# NB-Blue.net
KiCad netlist of a schematic drawn in Altium Designer
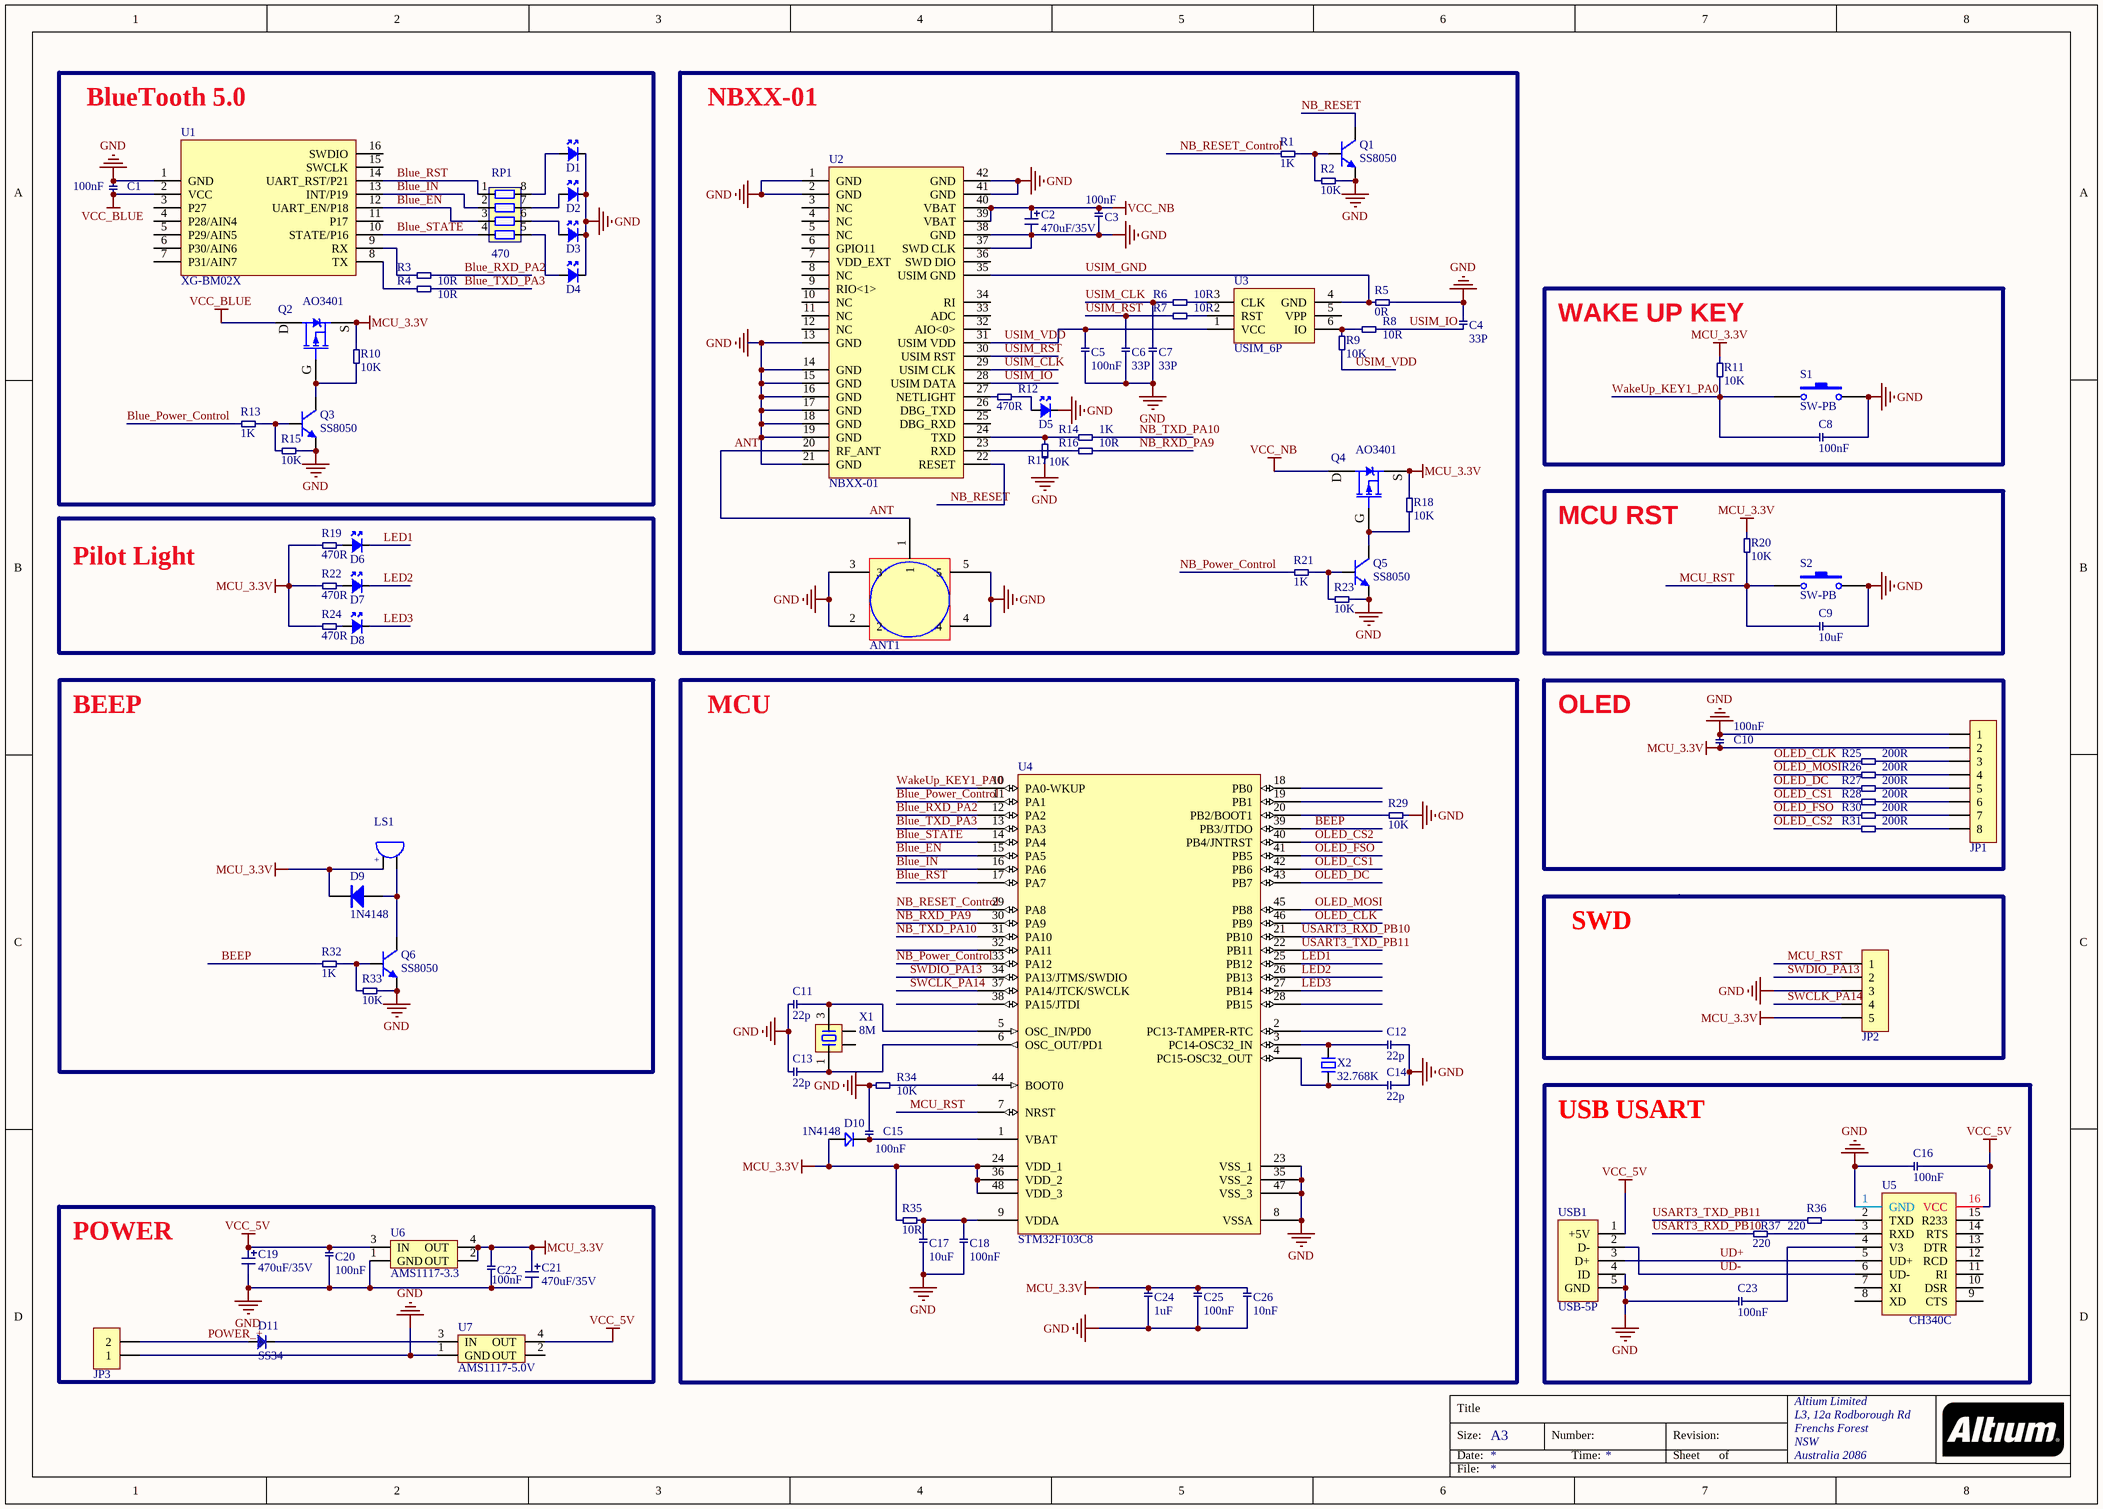
[diagram p0: NB-Blue.SchDoc]

(export (version "E")
  (design (tool "Eeschema 10.0.6"))
  (components
    (comp (ref "ANT1")
      (value "ANT")
      (footprint "SMA_FR")
      (description "SMA天线座")
      (libsource (lib "转接板顶板") (part "ANT"))
    )
    (comp (ref "C1") (value "100nF") (footprint "0603CC") (libsource (lib "LFZ@WLP") (part "cap")))
    (comp (ref "C2") (value "470uF/35V") (footprint "C3216") (libsource (lib "LFZ@WLP") (part "Ecap")))
    (comp (ref "C3") (value "100nF") (footprint "0603CC") (libsource (lib "LFZ@WLP") (part "cap")))
    (comp (ref "C4") (value "33P") (footprint "0603CC") (libsource (lib "LFZ@WLP") (part "cap")))
    (comp (ref "C5") (value "100nF") (footprint "0603CC") (libsource (lib "LFZ@WLP") (part "cap")))
    (comp (ref "C6") (value "33P") (footprint "0603CC") (libsource (lib "LFZ@WLP") (part "cap")))
    (comp (ref "C7") (value "33P") (footprint "0603CC") (libsource (lib "LFZ@WLP") (part "cap")))
    (comp (ref "C8") (value "100nF") (footprint "0603CC") (libsource (lib "LFZ@WLP") (part "cap")))
    (comp (ref "C9") (value "10uF") (footprint "0603CC") (libsource (lib "LFZ@WLP") (part "cap")))
    (comp (ref "C10") (value "100nF") (footprint "0603CC") (libsource (lib "LFZ@WLP") (part "cap")))
    (comp (ref "C11") (value "22p") (footprint "0603CC") (libsource (lib "LFZ@WLP") (part "cap")))
    (comp (ref "C12") (value "22p") (footprint "0603CC") (libsource (lib "LFZ@WLP") (part "cap")))
    (comp (ref "C13") (value "22p") (footprint "0603CC") (libsource (lib "LFZ@WLP") (part "cap")))
    (comp (ref "C14") (value "22p") (footprint "0603CC") (libsource (lib "LFZ@WLP") (part "cap")))
    (comp (ref "C15") (value "100nF") (footprint "0603CC") (libsource (lib "LFZ@WLP") (part "cap")))
    (comp (ref "C16") (value "100nF") (footprint "0603CC") (libsource (lib "LFZ@WLP") (part "cap")))
    (comp (ref "C17") (value "10uF") (footprint "0603CC") (libsource (lib "LFZ@WLP") (part "cap")))
    (comp (ref "C18") (value "100nF") (footprint "0603CC") (libsource (lib "LFZ@WLP") (part "cap")))
    (comp (ref "C19") (value "470uF/35V") (footprint "CD A(3216)") (libsource (lib "LFZ@WLP") (part "Ecap")))
    (comp (ref "C20") (value "100nF") (footprint "0603CC") (libsource (lib "LFZ@WLP") (part "cap")))
    (comp (ref "C21") (value "470uF/35V") (footprint "C3216") (libsource (lib "LFZ@WLP") (part "Ecap")))
    (comp (ref "C22") (value "100nF") (footprint "0603CC") (libsource (lib "LFZ@WLP") (part "cap")))
    (comp (ref "C23") (value "100nF") (footprint "0603CC") (libsource (lib "LFZ@WLP") (part "cap")))
    (comp (ref "C24") (value "1uF") (footprint "0603CC") (libsource (lib "LFZ@WLP") (part "cap")))
    (comp (ref "C25") (value "100nF") (footprint "0603CC") (libsource (lib "LFZ@WLP") (part "cap")))
    (comp (ref "C26") (value "10nF") (footprint "0603CC") (libsource (lib "LFZ@WLP") (part "cap")))
    (comp (ref "D1") (value "LED") (footprint "LED 0603G") (libsource (lib "LFZ@WLP") (part "LED")))
    (comp (ref "D2") (value "LED") (footprint "LED 0603G") (libsource (lib "LFZ@WLP") (part "LED")))
    (comp (ref "D3") (value "LED") (footprint "LED 0603G") (libsource (lib "LFZ@WLP") (part "LED")))
    (comp (ref "D4") (value "LED") (footprint "LED 0603G") (libsource (lib "LFZ@WLP") (part "LED")))
    (comp (ref "D5") (value "LED") (footprint "LED 0603G") (libsource (lib "LFZ@WLP") (part "LED")))
    (comp (ref "D6") (value "LED") (footprint "LED 3MM-G") (libsource (lib "LFZ@WLP") (part "LED")))
    (comp (ref "D7") (value "LED") (footprint "LED 3MM-G") (libsource (lib "LFZ@WLP") (part "LED")))
    (comp (ref "D8") (value "LED") (footprint "LED 3MM-G") (libsource (lib "LFZ@WLP") (part "LED")))
    (comp (ref "D9")
      (value "1N4148")
      (footprint "SOD-323")
      (description "高速开关二极管")
      (fields (field (name "版权归属") "源创客"))
      (libsource (lib "8.1   - 二极管-整流桥") (part "1N4148"))
    )
    (comp (ref "D10")
      (value "1N4148")
      (footprint "SOD-323")
      (libsource (lib "WarShip V3 STM32103封装库") (part "D"))
    )
    (comp (ref "D11") (value "SS34") (footprint "SMA") (libsource (lib "Diod") (part "Diod")))
    (comp (ref "JP1")
      (value "HDR-1X8")
      (footprint "HDR2.54-M-LI-8P")
      (description "8P接插件")
      (fields (field (name "版权归属") "源创客"))
      (libsource (lib "4.5   - 接插件-脚距2.54") (part "Header 8"))
    )
    (comp (ref "JP2")
      (value "HDR-1X5")
      (footprint "HDR2.54-LI-5P")
      (description "5P接插件")
      (fields (field (name "版权归属") "源创客"))
      (libsource (lib "4.5   - 接插件-脚距2.54") (part "Header 5"))
    )
    (comp (ref "JP3")
      (value "HDR-1X2")
      (footprint "XH2.54-WI-2P")
      (description "2P接插件")
      (fields (field (name "版权归属") "源创客"))
      (libsource (lib "4.5   - 接插件-脚距2.54") (part "Header 2"))
    )
    (comp (ref "LS1")
      (value "DC5V")
      (footprint "BEEP 5x9x5.5")
      (description "蜂鸣器")
      (fields (field (name "版权归属") "源创客"))
      (libsource (lib "15.1 - 未分类器件") (part "BEEP"))
    )
    (comp (ref "Q1")
      (value "SS8050")
      (footprint "SOT23-3N")
      (description "高频放大-NPN型")
      (fields (field (name "版权归属") "源创客"))
      (libsource (lib "6.2   - 三极管") (part "8050-SMD"))
    )
    (comp (ref "Q2")
      (value "AO3401")
      (footprint "SOT23-3N")
      (description "P沟道场效应管")
      (fields (field (name "版权归属") "源创客"))
      (libsource (lib "6.1   - 场效应管-可控硅") (part "SI2301"))
    )
    (comp (ref "Q3")
      (value "SS8050")
      (footprint "SOT23-3N")
      (description "高频放大-NPN型")
      (fields (field (name "版权归属") "源创客"))
      (libsource (lib "6.2   - 三极管") (part "8050-SMD"))
    )
    (comp (ref "Q4")
      (value "AO3401")
      (footprint "SOT23-3N")
      (description "P沟道场效应管")
      (fields (field (name "版权归属") "源创客"))
      (libsource (lib "6.1   - 场效应管-可控硅") (part "SI2301"))
    )
    (comp (ref "Q5")
      (value "SS8050")
      (footprint "SOT23-3N")
      (description "高频放大-NPN型")
      (fields (field (name "版权归属") "源创客"))
      (libsource (lib "6.2   - 三极管") (part "8050-SMD"))
    )
    (comp (ref "Q6")
      (value "SS8050")
      (footprint "SOT23-3N")
      (description "高频放大-NPN型")
      (fields (field (name "版权归属") "源创客"))
      (libsource (lib "6.2   - 三极管") (part "8050-SMD"))
    )
    (comp (ref "R1") (value "1K") (footprint "0603RR") (libsource (lib "LFZ@WLP") (part "res")))
    (comp (ref "R2") (value "10K") (footprint "0603RR") (libsource (lib "LFZ@WLP") (part "res")))
    (comp (ref "R3") (value "10R") (footprint "0603RR") (libsource (lib "LFZ@WLP") (part "res")))
    (comp (ref "R4") (value "10R") (footprint "0603RR") (libsource (lib "LFZ@WLP") (part "res")))
    (comp (ref "R5") (value "0R") (footprint "0603RR") (libsource (lib "LFZ@WLP") (part "res")))
    (comp (ref "R6") (value "10R") (footprint "0603RR") (libsource (lib "LFZ@WLP") (part "res")))
    (comp (ref "R7") (value "10R") (footprint "0603RR") (libsource (lib "LFZ@WLP") (part "res")))
    (comp (ref "R8") (value "10R") (footprint "0603RR") (libsource (lib "LFZ@WLP") (part "res")))
    (comp (ref "R9") (value "10K") (footprint "0603RR") (libsource (lib "LFZ@WLP") (part "res")))
    (comp (ref "R10") (value "10K") (footprint "0603RR") (libsource (lib "LFZ@WLP") (part "res")))
    (comp (ref "R11") (value "10K") (footprint "0603RR") (libsource (lib "LFZ@WLP") (part "res")))
    (comp (ref "R12") (value "470R") (footprint "0603RR") (libsource (lib "LFZ@WLP") (part "res")))
    (comp (ref "R13") (value "1K") (footprint "0603RR") (libsource (lib "LFZ@WLP") (part "res")))
    (comp (ref "R14") (value "1K") (footprint "0603RR") (libsource (lib "LFZ@WLP") (part "res")))
    (comp (ref "R15") (value "10K") (footprint "0603RR") (libsource (lib "LFZ@WLP") (part "res")))
    (comp (ref "R16") (value "10R") (footprint "0603RR") (libsource (lib "LFZ@WLP") (part "res")))
    (comp (ref "R17") (value "10K") (footprint "0603RR") (libsource (lib "LFZ@WLP") (part "res")))
    (comp (ref "R18") (value "10K") (footprint "0603RR") (libsource (lib "LFZ@WLP") (part "res")))
    (comp (ref "R19") (value "470R") (footprint "0603RR") (libsource (lib "LFZ@WLP") (part "res")))
    (comp (ref "R20") (value "10K") (footprint "0603RR") (libsource (lib "LFZ@WLP") (part "res")))
    (comp (ref "R21") (value "1K") (footprint "0603RR") (libsource (lib "LFZ@WLP") (part "res")))
    (comp (ref "R22") (value "470R") (footprint "0603RR") (libsource (lib "LFZ@WLP") (part "res")))
    (comp (ref "R23") (value "10K") (footprint "0603RR") (libsource (lib "LFZ@WLP") (part "res")))
    (comp (ref "R24") (value "470R") (footprint "0603RR") (libsource (lib "LFZ@WLP") (part "res")))
    (comp (ref "R25") (value "200R") (footprint "0603RR") (libsource (lib "LFZ@WLP") (part "res")))
    (comp (ref "R26") (value "200R") (footprint "0603RR") (libsource (lib "LFZ@WLP") (part "res")))
    (comp (ref "R27") (value "200R") (footprint "0603RR") (libsource (lib "LFZ@WLP") (part "res")))
    (comp (ref "R28") (value "200R") (footprint "0603RR") (libsource (lib "LFZ@WLP") (part "res")))
    (comp (ref "R29") (value "10K") (footprint "0603RR") (libsource (lib "LFZ@WLP") (part "res")))
    (comp (ref "R30") (value "200R") (footprint "0603RR") (libsource (lib "LFZ@WLP") (part "res")))
    (comp (ref "R31") (value "200R") (footprint "0603RR") (libsource (lib "LFZ@WLP") (part "res")))
    (comp (ref "R32") (value "1K") (footprint "0603RR") (libsource (lib "LFZ@WLP") (part "res")))
    (comp (ref "R33") (value "10K") (footprint "0603RR") (libsource (lib "LFZ@WLP") (part "res")))
    (comp (ref "R34") (value "10K") (footprint "0603RR") (libsource (lib "LFZ@WLP") (part "res")))
    (comp (ref "R35") (value "10R") (footprint "0603RR") (libsource (lib "LFZ@WLP") (part "res")))
    (comp (ref "R36") (value "220") (footprint "0603RR") (libsource (lib "LFZ@WLP") (part "res")))
    (comp (ref "R37") (value "220") (footprint "0603RR") (libsource (lib "LFZ@WLP") (part "res")))
    (comp (ref "RP1") (value "470") (footprint "4x0603") (libsource (lib "LFZ@WLP") (part "Resistor_Pack")))
    (comp (ref "S1")
      (value "SW-PB")
      (footprint "TSW SMD-6*6*6")
      (description "Switch")
      (fields (field (name "PUBLISHER") "Altium Limited"))
      (libsource (lib "开关及电源") (part "SW-PB"))
    )
    (comp (ref "S2")
      (value "SW-PB")
      (footprint "TSW SMD-4*4*1.5")
      (description "Switch")
      (fields (field (name "PUBLISHER") "Altium Limited"))
      (libsource (lib "开关及电源") (part "SW-PB"))
    )
    (comp (ref "U1") (value "XG-BM02X") (footprint "XG-BM02X") (libsource (lib "XG-BM02") (part "XG-BM02X")))
    (comp (ref "U2")
      (value "NBXX-01")
      (footprint "X_LSD4NBN-LB05000001")
      (libsource (lib "XG-BM02") (part "NB"))
    )
    (comp (ref "U3") (value "USIM_6P") (footprint "SIM 6P 自弹") (libsource (lib "XG-BM02") (part "USIM-6P")))
    (comp (ref "U4")
      (value "STM32F103C8")
      (footprint "LQFP48 7X7_M")
      (description "Flaah:64/RAM:20/IO:36")
      (fields (field (name "版权归属") "源创客"))
      (libsource (lib "2.1   - STM32系列单片机") (part "STM32F103C8"))
    )
    (comp (ref "U5") (value "CH340C") (footprint "SOP16_L") (libsource (lib "LFZ@WLP") (part "CH340C")))
    (comp (ref "U6")
      (value "AMS1117-3.3")
      (footprint "SOT223_N")
      (libsource (lib "WarShip V3 STM32103封装库") (part "AMS1117"))
    )
    (comp (ref "U7")
      (value "AMS1117-5.0V")
      (footprint "SOT223_N")
      (libsource (lib "WarShip V3 STM32103封装库") (part "AMS1117"))
    )
    (comp (ref "USB1")
      (value "USB-5P")
      (footprint "USB-MICRO_A")
      (description "微型USB母座")
      (fields (field (name "版权归属") "源创客"))
      (libsource (lib "4.1   - 接口类") (part "USB-5P"))
    )
    (comp (ref "X1")
      (value "8M")
      (footprint "OSC 3225-4P")
      (description "4脚无源晶振")
      (fields (field (name "版权归属") "源创客"))
      (libsource (lib "10.1 - 保险丝-晶振") (part "XTAL-4P"))
    )
    (comp (ref "X2")
      (value "32.768K")
      (footprint "OSC 3215-2P")
      (description "2脚无源脚晶振")
      (fields (field (name "版权归属") "源创客"))
      (libsource (lib "10.1 - 保险丝-晶振") (part "XTAL-2P"))
    )
  )
  (nets
    (net (code "1") (name "/ANT") (class "Default")
      (node (ref "ANT1") (pin "1") (pinfunction "1_1") (pintype "passive"))
      (node (ref "U2") (pin "20") (pinfunction "RF_ANT_20") (pintype "passive"))
    )
    (net (code "2") (name "/BEEP") (class "Default")
      (node (ref "R32") (pin "1") (pinfunction "1_1") (pintype "passive"))
      (node (ref "U4") (pin "39") (pinfunction "PB3/JTDO_39") (pintype "bidirectional"))
    )
    (net (code "3") (name "/Blue_EN") (class "Default")
      (node (ref "RP1") (pin "3") (pinfunction "3_3") (pintype "passive"))
      (node (ref "U1") (pin "12") (pinfunction "UART_EN/P18_12") (pintype "passive"))
      (node (ref "U4") (pin "15") (pinfunction "PA5_15") (pintype "bidirectional"))
    )
    (net (code "4") (name "/Blue_IN") (class "Default")
      (node (ref "RP1") (pin "2") (pinfunction "2_2") (pintype "passive"))
      (node (ref "U1") (pin "13") (pinfunction "INT/P19_13") (pintype "passive"))
      (node (ref "U4") (pin "16") (pinfunction "PA6_16") (pintype "bidirectional"))
    )
    (net (code "5") (name "/Blue_Power_Control") (class "Default")
      (node (ref "R13") (pin "1") (pinfunction "1_1") (pintype "passive"))
      (node (ref "U4") (pin "11") (pinfunction "PA1_11") (pintype "bidirectional"))
    )
    (net (code "6") (name "/Blue_RST") (class "Default")
      (node (ref "RP1") (pin "1") (pinfunction "1_1") (pintype "passive"))
      (node (ref "U1") (pin "14") (pinfunction "UART_RST/P21_14") (pintype "passive"))
      (node (ref "U4") (pin "17") (pinfunction "PA7_17") (pintype "bidirectional"))
    )
    (net (code "7") (name "/Blue_RXD_PA2") (class "Default")
      (node (ref "R3") (pin "2") (pinfunction "2_2") (pintype "passive"))
      (node (ref "U4") (pin "12") (pinfunction "PA2_12") (pintype "bidirectional"))
    )
    (net (code "8") (name "/Blue_STATE") (class "Default")
      (node (ref "RP1") (pin "4") (pinfunction "4_4") (pintype "passive"))
      (node (ref "U1") (pin "10") (pinfunction "STATE/P16_10") (pintype "passive"))
      (node (ref "U4") (pin "14") (pinfunction "PA4_14") (pintype "bidirectional"))
    )
    (net (code "9") (name "/Blue_TXD_PA3") (class "Default")
      (node (ref "R4") (pin "2") (pinfunction "2_2") (pintype "passive"))
      (node (ref "U4") (pin "13") (pinfunction "PA3_13") (pintype "bidirectional"))
    )
    (net (code "10") (name "/LED1") (class "Default")
      (node (ref "D6") (pin "2") (pinfunction "CATHODE_2") (pintype "passive"))
      (node (ref "U4") (pin "25") (pinfunction "PB12_25") (pintype "bidirectional"))
    )
    (net (code "11") (name "/LED2") (class "Default")
      (node (ref "D7") (pin "2") (pinfunction "CATHODE_2") (pintype "passive"))
      (node (ref "U4") (pin "26") (pinfunction "PB13_26") (pintype "bidirectional"))
    )
    (net (code "12") (name "/LED3") (class "Default")
      (node (ref "D8") (pin "2") (pinfunction "CATHODE_2") (pintype "passive"))
      (node (ref "U4") (pin "27") (pinfunction "PB14_27") (pintype "bidirectional"))
    )
    (net (code "13") (name "/MCU_RST") (class "Default")
      (node (ref "C9") (pin "2") (pinfunction "2_2") (pintype "passive"))
      (node (ref "JP2") (pin "1") (pinfunction "1_1") (pintype "passive"))
      (node (ref "R20") (pin "1") (pinfunction "1_1") (pintype "passive"))
      (node (ref "S2") (pin "1") (pinfunction "1_1") (pintype "passive"))
      (node (ref "U4") (pin "7") (pinfunction "NRST_7") (pintype "bidirectional"))
    )
    (net (code "14") (name "/NB_Power_Control") (class "Default")
      (node (ref "R21") (pin "1") (pinfunction "1_1") (pintype "passive"))
      (node (ref "U4") (pin "33") (pinfunction "PA12_33") (pintype "bidirectional"))
    )
    (net (code "15") (name "/NB_RESET") (class "Default")
      (node (ref "Q1") (pin "3") (pinfunction "C_3") (pintype "passive"))
      (node (ref "U2") (pin "22") (pinfunction "RESET_22") (pintype "passive"))
    )
    (net (code "16") (name "/NB_RESET_Control") (class "Default")
      (node (ref "R1") (pin "1") (pinfunction "1_1") (pintype "passive"))
      (node (ref "U4") (pin "29") (pinfunction "PA8_29") (pintype "bidirectional"))
    )
    (net (code "17") (name "/NB_RXD_PA9") (class "Default")
      (node (ref "R16") (pin "2") (pinfunction "2_2") (pintype "passive"))
      (node (ref "U4") (pin "30") (pinfunction "PA9_30") (pintype "bidirectional"))
    )
    (net (code "18") (name "/NB_TXD_PA10") (class "Default")
      (node (ref "R14") (pin "2") (pinfunction "2_2") (pintype "passive"))
      (node (ref "U4") (pin "31") (pinfunction "PA10_31") (pintype "bidirectional"))
    )
    (net (code "19") (name "/OLED_CLK") (class "Default")
      (node (ref "R25") (pin "1") (pinfunction "1_1") (pintype "passive"))
      (node (ref "U4") (pin "46") (pinfunction "PB9_46") (pintype "bidirectional"))
    )
    (net (code "20") (name "/OLED_CS1") (class "Default")
      (node (ref "R28") (pin "1") (pinfunction "1_1") (pintype "passive"))
      (node (ref "U4") (pin "42") (pinfunction "PB6_42") (pintype "bidirectional"))
    )
    (net (code "21") (name "/OLED_CS2") (class "Default")
      (node (ref "R31") (pin "1") (pinfunction "1_1") (pintype "passive"))
      (node (ref "U4") (pin "40") (pinfunction "PB4/JNTRST_40") (pintype "bidirectional"))
    )
    (net (code "22") (name "/OLED_DC") (class "Default")
      (node (ref "R27") (pin "1") (pinfunction "1_1") (pintype "passive"))
      (node (ref "U4") (pin "43") (pinfunction "PB7_43") (pintype "bidirectional"))
    )
    (net (code "23") (name "/OLED_FSO") (class "Default")
      (node (ref "R30") (pin "1") (pinfunction "1_1") (pintype "passive"))
      (node (ref "U4") (pin "41") (pinfunction "PB5_41") (pintype "bidirectional"))
    )
    (net (code "24") (name "/OLED_MOSI") (class "Default")
      (node (ref "R26") (pin "1") (pinfunction "1_1") (pintype "passive"))
      (node (ref "U4") (pin "45") (pinfunction "PB8_45") (pintype "bidirectional"))
    )
    (net (code "25") (name "/POWER_+") (class "Default")
      (node (ref "D11") (pin "1") (pinfunction "ANODE_1") (pintype "passive"))
      (node (ref "JP3") (pin "2") (pinfunction "2_2") (pintype "passive"))
    )
    (net (code "26") (name "/SWCLK_PA14") (class "Default")
      (node (ref "JP2") (pin "4") (pinfunction "4_4") (pintype "passive"))
      (node (ref "U4") (pin "37") (pinfunction "PA14/JTCK/SWCLK_37") (pintype "bidirectional"))
    )
    (net (code "27") (name "/SWDIO_PA13") (class "Default")
      (node (ref "JP2") (pin "2") (pinfunction "2_2") (pintype "passive"))
      (node (ref "U4") (pin "34") (pinfunction "PA13/JTMS/SWDIO_34") (pintype "bidirectional"))
    )
    (net (code "28") (name "/UD+") (class "Default")
      (node (ref "U5") (pin "5") (pinfunction "UD+_5") (pintype "passive"))
      (node (ref "USB1") (pin "3") (pinfunction "D+_3") (pintype "passive"))
    )
    (net (code "29") (name "/UD-") (class "Default")
      (node (ref "U5") (pin "6") (pinfunction "UD-_6") (pintype "passive"))
      (node (ref "USB1") (pin "2") (pinfunction "D-_2") (pintype "passive"))
    )
    (net (code "30") (name "/USART3_RXD_PB10") (class "Default")
      (node (ref "R37") (pin "1") (pinfunction "1_1") (pintype "passive"))
      (node (ref "U4") (pin "21") (pinfunction "PB10_21") (pintype "bidirectional"))
    )
    (net (code "31") (name "/USART3_TXD_PB11") (class "Default")
      (node (ref "R36") (pin "1") (pinfunction "1_1") (pintype "passive"))
      (node (ref "U4") (pin "22") (pinfunction "PB11_22") (pintype "bidirectional"))
    )
    (net (code "32") (name "/USIM_CLK") (class "Default")
      (node (ref "C7") (pin "2") (pinfunction "2_2") (pintype "passive"))
      (node (ref "R6") (pin "1") (pinfunction "1_1") (pintype "passive"))
      (node (ref "U2") (pin "29") (pinfunction "USIM_CLK_29") (pintype "passive"))
    )
    (net (code "33") (name "/USIM_GND") (class "Default")
      (node (ref "R5") (pin "1") (pinfunction "1_1") (pintype "passive"))
      (node (ref "U2") (pin "35") (pinfunction "USIM_GND_35") (pintype "passive"))
      (node (ref "U3") (pin "4") (pinfunction "GND_4") (pintype "passive"))
    )
    (net (code "34") (name "/USIM_IO") (class "Default")
      (node (ref "C4") (pin "1") (pinfunction "1_1") (pintype "passive"))
      (node (ref "R8") (pin "1") (pinfunction "1_1") (pintype "passive"))
      (node (ref "U2") (pin "28") (pinfunction "USIM_DATA_28") (pintype "passive"))
    )
    (net (code "35") (name "/USIM_RST") (class "Default")
      (node (ref "C6") (pin "2") (pinfunction "2_2") (pintype "passive"))
      (node (ref "R7") (pin "1") (pinfunction "1_1") (pintype "passive"))
      (node (ref "U2") (pin "30") (pinfunction "USIM_RST_30") (pintype "passive"))
    )
    (net (code "36") (name "/USIM_VDD") (class "Default")
      (node (ref "C5") (pin "2") (pinfunction "2_2") (pintype "passive"))
      (node (ref "R9") (pin "1") (pinfunction "1_1") (pintype "passive"))
      (node (ref "U2") (pin "31") (pinfunction "USIM_VDD_31") (pintype "passive"))
      (node (ref "U3") (pin "1") (pinfunction "VCC_1") (pintype "passive"))
    )
    (net (code "37") (name "/WakeUp_KEY1_PA0") (class "Default")
      (node (ref "C8") (pin "1") (pinfunction "1_1") (pintype "passive"))
      (node (ref "R11") (pin "1") (pinfunction "1_1") (pintype "passive"))
      (node (ref "S1") (pin "1") (pinfunction "1_1") (pintype "passive"))
      (node (ref "U4") (pin "10") (pinfunction "PA0-WKUP_10") (pintype "bidirectional"))
    )
    (net (code "38") (name "GND") (class "Default")
      (node (ref "ANT1") (pin "2") (pinfunction "2_2") (pintype "passive"))
      (node (ref "ANT1") (pin "3") (pinfunction "3_3") (pintype "passive"))
      (node (ref "ANT1") (pin "4") (pinfunction "4_4") (pintype "passive"))
      (node (ref "ANT1") (pin "5") (pinfunction "5_5") (pintype "passive"))
      (node (ref "C1") (pin "2") (pinfunction "2_2") (pintype "passive"))
      (node (ref "C10") (pin "2") (pinfunction "2_2") (pintype "passive"))
      (node (ref "C11") (pin "1") (pinfunction "1_1") (pintype "passive"))
      (node (ref "C12") (pin "2") (pinfunction "2_2") (pintype "passive"))
      (node (ref "C13") (pin "1") (pinfunction "1_1") (pintype "passive"))
      (node (ref "C14") (pin "2") (pinfunction "2_2") (pintype "passive"))
      (node (ref "C15") (pin "2") (pinfunction "2_2") (pintype "passive"))
      (node (ref "C16") (pin "2") (pinfunction "2_2") (pintype "passive"))
      (node (ref "C17") (pin "1") (pinfunction "1_1") (pintype "passive"))
      (node (ref "C18") (pin "1") (pinfunction "1_1") (pintype "passive"))
      (node (ref "C19") (pin "2") (pinfunction "2_2") (pintype "passive"))
      (node (ref "C2") (pin "2") (pinfunction "2_2") (pintype "passive"))
      (node (ref "C20") (pin "1") (pinfunction "1_1") (pintype "passive"))
      (node (ref "C21") (pin "2") (pinfunction "2_2") (pintype "passive"))
      (node (ref "C22") (pin "1") (pinfunction "1_1") (pintype "passive"))
      (node (ref "C23") (pin "2") (pinfunction "2_2") (pintype "passive"))
      (node (ref "C24") (pin "1") (pinfunction "1_1") (pintype "passive"))
      (node (ref "C25") (pin "1") (pinfunction "1_1") (pintype "passive"))
      (node (ref "C26") (pin "1") (pinfunction "1_1") (pintype "passive"))
      (node (ref "C3") (pin "1") (pinfunction "1_1") (pintype "passive"))
      (node (ref "C4") (pin "2") (pinfunction "2_2") (pintype "passive"))
      (node (ref "C5") (pin "1") (pinfunction "1_1") (pintype "passive"))
      (node (ref "C6") (pin "1") (pinfunction "1_1") (pintype "passive"))
      (node (ref "C7") (pin "1") (pinfunction "1_1") (pintype "passive"))
      (node (ref "C8") (pin "2") (pinfunction "2_2") (pintype "passive"))
      (node (ref "C9") (pin "1") (pinfunction "1_1") (pintype "passive"))
      (node (ref "D1") (pin "2") (pinfunction "CATHODE_2") (pintype "passive"))
      (node (ref "D2") (pin "2") (pinfunction "CATHODE_2") (pintype "passive"))
      (node (ref "D3") (pin "2") (pinfunction "CATHODE_2") (pintype "passive"))
      (node (ref "D4") (pin "2") (pinfunction "CATHODE_2") (pintype "passive"))
      (node (ref "D5") (pin "2") (pinfunction "CATHODE_2") (pintype "passive"))
      (node (ref "JP1") (pin "1") (pinfunction "1_1") (pintype "passive"))
      (node (ref "JP2") (pin "3") (pinfunction "3_3") (pintype "passive"))
      (node (ref "JP3") (pin "1") (pinfunction "1_1") (pintype "passive"))
      (node (ref "Q1") (pin "2") (pinfunction "E_2") (pintype "passive"))
      (node (ref "Q3") (pin "2") (pinfunction "E_2") (pintype "passive"))
      (node (ref "Q5") (pin "2") (pinfunction "E_2") (pintype "passive"))
      (node (ref "Q6") (pin "2") (pinfunction "E_2") (pintype "passive"))
      (node (ref "R15") (pin "2") (pinfunction "2_2") (pintype "passive"))
      (node (ref "R17") (pin "2") (pinfunction "2_2") (pintype "passive"))
      (node (ref "R2") (pin "2") (pinfunction "2_2") (pintype "passive"))
      (node (ref "R23") (pin "2") (pinfunction "2_2") (pintype "passive"))
      (node (ref "R29") (pin "2") (pinfunction "2_2") (pintype "passive"))
      (node (ref "R33") (pin "2") (pinfunction "2_2") (pintype "passive"))
      (node (ref "R34") (pin "1") (pinfunction "1_1") (pintype "passive"))
      (node (ref "R5") (pin "2") (pinfunction "2_2") (pintype "passive"))
      (node (ref "S1") (pin "2") (pinfunction "2_2") (pintype "passive"))
      (node (ref "S2") (pin "2") (pinfunction "2_2") (pintype "passive"))
      (node (ref "U1") (pin "1") (pinfunction "GND_1") (pintype "passive"))
      (node (ref "U2") (pin "1") (pinfunction "GND_1") (pintype "passive"))
      (node (ref "U2") (pin "13") (pinfunction "GND_13") (pintype "passive"))
      (node (ref "U2") (pin "14") (pinfunction "GND_14") (pintype "passive"))
      (node (ref "U2") (pin "15") (pinfunction "GND_15") (pintype "passive"))
      (node (ref "U2") (pin "16") (pinfunction "GND_16") (pintype "passive"))
      (node (ref "U2") (pin "17") (pinfunction "GND_17") (pintype "passive"))
      (node (ref "U2") (pin "18") (pinfunction "GND_18") (pintype "passive"))
      (node (ref "U2") (pin "19") (pinfunction "GND_19") (pintype "passive"))
      (node (ref "U2") (pin "2") (pinfunction "GND_2") (pintype "passive"))
      (node (ref "U2") (pin "21") (pinfunction "GND_21") (pintype "passive"))
      (node (ref "U2") (pin "37") (pinfunction "SWD_CLK_37") (pintype "passive"))
      (node (ref "U2") (pin "38") (pinfunction "GND_38") (pintype "passive"))
      (node (ref "U2") (pin "41") (pinfunction "GND_41") (pintype "passive"))
      (node (ref "U2") (pin "42") (pinfunction "GND_42") (pintype "passive"))
      (node (ref "U4") (pin "23") (pinfunction "VSS_1_23") (pintype "power_in"))
      (node (ref "U4") (pin "35") (pinfunction "VSS_2_35") (pintype "power_in"))
      (node (ref "U4") (pin "47") (pinfunction "VSS_3_47") (pintype "power_in"))
      (node (ref "U4") (pin "8") (pinfunction "VSSA_8") (pintype "power_in"))
      (node (ref "U5") (pin "1") (pinfunction "GND_1") (pintype "passive"))
      (node (ref "U6") (pin "1") (pinfunction "GND_1") (pintype "passive"))
      (node (ref "U7") (pin "1") (pinfunction "GND_1") (pintype "passive"))
      (node (ref "USB1") (pin "4") (pinfunction "ID_4") (pintype "passive"))
      (node (ref "USB1") (pin "5") (pinfunction "GND_5") (pintype "passive"))
    )
    (net (code "39") (name "MCU_3.3V") (class "Default")
      (node (ref "C10") (pin "1") (pinfunction "1_1") (pintype "passive"))
      (node (ref "C21") (pin "1") (pinfunction "1_1") (pintype "passive"))
      (node (ref "C22") (pin "2") (pinfunction "2_2") (pintype "passive"))
      (node (ref "C24") (pin "2") (pinfunction "2_2") (pintype "passive"))
      (node (ref "C25") (pin "2") (pinfunction "2_2") (pintype "passive"))
      (node (ref "C26") (pin "2") (pinfunction "2_2") (pintype "passive"))
      (node (ref "D10") (pin "1") (pintype "passive"))
      (node (ref "D9") (pin "2") (pinfunction "K_2") (pintype "passive"))
      (node (ref "JP1") (pin "2") (pinfunction "2_2") (pintype "passive"))
      (node (ref "JP2") (pin "5") (pinfunction "5_5") (pintype "passive"))
      (node (ref "LS1") (pin "1") (pinfunction "1_1") (pintype "passive"))
      (node (ref "Q2") (pin "2") (pinfunction "S_2") (pintype "passive"))
      (node (ref "Q4") (pin "2") (pinfunction "S_2") (pintype "passive"))
      (node (ref "R10") (pin "2") (pinfunction "2_2") (pintype "passive"))
      (node (ref "R11") (pin "2") (pinfunction "2_2") (pintype "passive"))
      (node (ref "R18") (pin "2") (pinfunction "2_2") (pintype "passive"))
      (node (ref "R19") (pin "1") (pinfunction "1_1") (pintype "passive"))
      (node (ref "R20") (pin "2") (pinfunction "2_2") (pintype "passive"))
      (node (ref "R22") (pin "1") (pinfunction "1_1") (pintype "passive"))
      (node (ref "R24") (pin "1") (pinfunction "1_1") (pintype "passive"))
      (node (ref "R35") (pin "1") (pinfunction "1_1") (pintype "passive"))
      (node (ref "U4") (pin "24") (pinfunction "VDD_1_24") (pintype "power_in"))
      (node (ref "U4") (pin "36") (pinfunction "VDD_2_36") (pintype "power_in"))
      (node (ref "U4") (pin "48") (pinfunction "VDD_3_48") (pintype "power_in"))
      (node (ref "U6") (pin "2") (pinfunction "OUT_2") (pintype "passive"))
      (node (ref "U6") (pin "4") (pinfunction "OUT_4") (pintype "passive"))
    )
    (net (code "40") (name "Net-(D1-ANODE)") (class "Default")
      (node (ref "D1") (pin "1") (pinfunction "ANODE_1") (pintype "passive"))
      (node (ref "RP1") (pin "8") (pinfunction "8_8") (pintype "passive"))
    )
    (net (code "41") (name "Net-(D2-ANODE)") (class "Default")
      (node (ref "D2") (pin "1") (pinfunction "ANODE_1") (pintype "passive"))
      (node (ref "RP1") (pin "7") (pinfunction "7_7") (pintype "passive"))
    )
    (net (code "42") (name "Net-(D3-ANODE)") (class "Default")
      (node (ref "D3") (pin "1") (pinfunction "ANODE_1") (pintype "passive"))
      (node (ref "RP1") (pin "6") (pinfunction "6_6") (pintype "passive"))
    )
    (net (code "43") (name "Net-(D4-ANODE)") (class "Default")
      (node (ref "D4") (pin "1") (pinfunction "ANODE_1") (pintype "passive"))
      (node (ref "RP1") (pin "5") (pinfunction "5_5") (pintype "passive"))
    )
    (net (code "44") (name "Net-(D5-ANODE)") (class "Default")
      (node (ref "D5") (pin "1") (pinfunction "ANODE_1") (pintype "passive"))
      (node (ref "R12") (pin "2") (pinfunction "2_2") (pintype "passive"))
    )
    (net (code "45") (name "Net-(D6-ANODE)") (class "Default")
      (node (ref "D6") (pin "1") (pinfunction "ANODE_1") (pintype "passive"))
      (node (ref "R19") (pin "2") (pinfunction "2_2") (pintype "passive"))
    )
    (net (code "46") (name "Net-(D7-ANODE)") (class "Default")
      (node (ref "D7") (pin "1") (pinfunction "ANODE_1") (pintype "passive"))
      (node (ref "R22") (pin "2") (pinfunction "2_2") (pintype "passive"))
    )
    (net (code "47") (name "Net-(D8-ANODE)") (class "Default")
      (node (ref "D8") (pin "1") (pinfunction "ANODE_1") (pintype "passive"))
      (node (ref "R24") (pin "2") (pinfunction "2_2") (pintype "passive"))
    )
    (net (code "48") (name "Net-(D9-A)") (class "Default")
      (node (ref "D9") (pin "1") (pinfunction "A_1") (pintype "passive"))
      (node (ref "LS1") (pin "2") (pinfunction "2_2") (pintype "passive"))
      (node (ref "Q6") (pin "3") (pinfunction "C_3") (pintype "passive"))
    )
    (net (code "49") (name "Net-(D11-CATHODE)") (class "Default")
      (node (ref "D11") (pin "2") (pinfunction "CATHODE_2") (pintype "passive"))
      (node (ref "U7") (pin "3") (pinfunction "IN_3") (pintype "passive"))
    )
    (net (code "50") (name "Net-(JP1-Pad3)") (class "Default")
      (node (ref "JP1") (pin "3") (pinfunction "3_3") (pintype "passive"))
      (node (ref "R25") (pin "2") (pinfunction "2_2") (pintype "passive"))
    )
    (net (code "51") (name "Net-(JP1-Pad4)") (class "Default")
      (node (ref "JP1") (pin "4") (pinfunction "4_4") (pintype "passive"))
      (node (ref "R26") (pin "2") (pinfunction "2_2") (pintype "passive"))
    )
    (net (code "52") (name "Net-(JP1-Pad5)") (class "Default")
      (node (ref "JP1") (pin "5") (pinfunction "5_5") (pintype "passive"))
      (node (ref "R27") (pin "2") (pinfunction "2_2") (pintype "passive"))
    )
    (net (code "53") (name "Net-(JP1-Pad6)") (class "Default")
      (node (ref "JP1") (pin "6") (pinfunction "6_6") (pintype "passive"))
      (node (ref "R28") (pin "2") (pinfunction "2_2") (pintype "passive"))
    )
    (net (code "54") (name "Net-(JP1-Pad7)") (class "Default")
      (node (ref "JP1") (pin "7") (pinfunction "7_7") (pintype "passive"))
      (node (ref "R30") (pin "2") (pinfunction "2_2") (pintype "passive"))
    )
    (net (code "55") (name "Net-(JP1-Pad8)") (class "Default")
      (node (ref "JP1") (pin "8") (pinfunction "8_8") (pintype "passive"))
      (node (ref "R31") (pin "2") (pinfunction "2_2") (pintype "passive"))
    )
    (net (code "56") (name "Net-(Q1-B)") (class "Default")
      (node (ref "Q1") (pin "1") (pinfunction "B_1") (pintype "passive"))
      (node (ref "R1") (pin "2") (pinfunction "2_2") (pintype "passive"))
      (node (ref "R2") (pin "1") (pinfunction "1_1") (pintype "passive"))
    )
    (net (code "57") (name "Net-(Q2-G)") (class "Default")
      (node (ref "Q2") (pin "1") (pinfunction "G_1") (pintype "passive"))
      (node (ref "Q3") (pin "3") (pinfunction "C_3") (pintype "passive"))
      (node (ref "R10") (pin "1") (pinfunction "1_1") (pintype "passive"))
    )
    (net (code "58") (name "Net-(Q3-B)") (class "Default")
      (node (ref "Q3") (pin "1") (pinfunction "B_1") (pintype "passive"))
      (node (ref "R13") (pin "2") (pinfunction "2_2") (pintype "passive"))
      (node (ref "R15") (pin "1") (pinfunction "1_1") (pintype "passive"))
    )
    (net (code "59") (name "Net-(Q4-G)") (class "Default")
      (node (ref "Q4") (pin "1") (pinfunction "G_1") (pintype "passive"))
      (node (ref "Q5") (pin "3") (pinfunction "C_3") (pintype "passive"))
      (node (ref "R18") (pin "1") (pinfunction "1_1") (pintype "passive"))
    )
    (net (code "60") (name "Net-(Q5-B)") (class "Default")
      (node (ref "Q5") (pin "1") (pinfunction "B_1") (pintype "passive"))
      (node (ref "R21") (pin "2") (pinfunction "2_2") (pintype "passive"))
      (node (ref "R23") (pin "1") (pinfunction "1_1") (pintype "passive"))
    )
    (net (code "61") (name "Net-(Q6-B)") (class "Default")
      (node (ref "Q6") (pin "1") (pinfunction "B_1") (pintype "passive"))
      (node (ref "R32") (pin "2") (pinfunction "2_2") (pintype "passive"))
      (node (ref "R33") (pin "1") (pinfunction "1_1") (pintype "passive"))
    )
    (net (code "62") (name "Net-(U1-RX)") (class "Default")
      (node (ref "R3") (pin "1") (pinfunction "1_1") (pintype "passive"))
      (node (ref "U1") (pin "9") (pinfunction "RX_9") (pintype "passive"))
    )
    (net (code "63") (name "Net-(U1-TX)") (class "Default")
      (node (ref "R4") (pin "1") (pinfunction "1_1") (pintype "passive"))
      (node (ref "U1") (pin "8") (pinfunction "TX_8") (pintype "passive"))
    )
    (net (code "64") (name "Net-(U2-NETLIGHT)") (class "Default")
      (node (ref "R12") (pin "1") (pinfunction "1_1") (pintype "passive"))
      (node (ref "U2") (pin "27") (pinfunction "NETLIGHT_27") (pintype "passive"))
    )
    (net (code "65") (name "Net-(U2-RXD)") (class "Default")
      (node (ref "R16") (pin "1") (pinfunction "1_1") (pintype "passive"))
      (node (ref "U2") (pin "23") (pinfunction "RXD_23") (pintype "passive"))
    )
    (net (code "66") (name "Net-(U2-TXD)") (class "Default")
      (node (ref "R14") (pin "1") (pinfunction "1_1") (pintype "passive"))
      (node (ref "R17") (pin "1") (pinfunction "1_1") (pintype "passive"))
      (node (ref "U2") (pin "24") (pinfunction "TXD_24") (pintype "passive"))
    )
    (net (code "67") (name "Net-(U3-CLK)") (class "Default")
      (node (ref "R6") (pin "2") (pinfunction "2_2") (pintype "passive"))
      (node (ref "U3") (pin "3") (pinfunction "CLK_3") (pintype "passive"))
    )
    (net (code "68") (name "Net-(U3-IO)") (class "Default")
      (node (ref "R8") (pin "2") (pinfunction "2_2") (pintype "passive"))
      (node (ref "R9") (pin "2") (pinfunction "2_2") (pintype "passive"))
      (node (ref "U3") (pin "6") (pinfunction "IO_6") (pintype "passive"))
    )
    (net (code "69") (name "Net-(U3-RST)") (class "Default")
      (node (ref "R7") (pin "2") (pinfunction "2_2") (pintype "passive"))
      (node (ref "U3") (pin "2") (pinfunction "RST_2") (pintype "passive"))
    )
    (net (code "70") (name "Net-(U4-BOOT0)") (class "Default")
      (node (ref "R34") (pin "2") (pinfunction "2_2") (pintype "passive"))
      (node (ref "U4") (pin "44") (pinfunction "BOOT0_44") (pintype "input"))
    )
    (net (code "71") (name "Net-(U4-OSC_IN{slash}PD0)") (class "Default")
      (node (ref "C11") (pin "2") (pinfunction "2_2") (pintype "passive"))
      (node (ref "U4") (pin "5") (pinfunction "OSC_IN/PD0_5") (pintype "input"))
      (node (ref "X1") (pin "3") (pinfunction "3_3") (pintype "passive"))
    )
    (net (code "72") (name "Net-(U4-OSC_OUT{slash}PD1)") (class "Default")
      (node (ref "C13") (pin "2") (pinfunction "2_2") (pintype "passive"))
      (node (ref "U4") (pin "6") (pinfunction "OSC_OUT/PD1_6") (pintype "output"))
      (node (ref "X1") (pin "1") (pinfunction "1_1") (pintype "passive"))
    )
    (net (code "73") (name "Net-(U4-PB2{slash}BOOT1)") (class "Default")
      (node (ref "R29") (pin "1") (pinfunction "1_1") (pintype "passive"))
      (node (ref "U4") (pin "20") (pinfunction "PB2/BOOT1_20") (pintype "bidirectional"))
    )
    (net (code "74") (name "Net-(U4-PC14-OSC32_IN)") (class "Default")
      (node (ref "C12") (pin "1") (pinfunction "1_1") (pintype "passive"))
      (node (ref "U4") (pin "3") (pinfunction "PC14-OSC32_IN_3") (pintype "bidirectional"))
      (node (ref "X2") (pin "2") (pinfunction "2_2") (pintype "passive"))
    )
    (net (code "75") (name "Net-(U4-PC15-OSC32_OUT)") (class "Default")
      (node (ref "C14") (pin "1") (pinfunction "1_1") (pintype "passive"))
      (node (ref "U4") (pin "4") (pinfunction "PC15-OSC32_OUT_4") (pintype "bidirectional"))
      (node (ref "X2") (pin "1") (pinfunction "1_1") (pintype "passive"))
    )
    (net (code "76") (name "Net-(U4-VBAT)") (class "Default")
      (node (ref "C15") (pin "1") (pinfunction "1_1") (pintype "passive"))
      (node (ref "D10") (pin "2") (pintype "passive"))
      (node (ref "U4") (pin "1") (pinfunction "VBAT_1") (pintype "power_in"))
    )
    (net (code "77") (name "Net-(U4-VDDA)") (class "Default")
      (node (ref "C17") (pin "2") (pinfunction "2_2") (pintype "passive"))
      (node (ref "C18") (pin "2") (pinfunction "2_2") (pintype "passive"))
      (node (ref "R35") (pin "2") (pinfunction "2_2") (pintype "passive"))
      (node (ref "U4") (pin "9") (pinfunction "VDDA_9") (pintype "power_in"))
    )
    (net (code "78") (name "Net-(U5-RXD)") (class "Default")
      (node (ref "R37") (pin "2") (pinfunction "2_2") (pintype "passive"))
      (node (ref "U5") (pin "3") (pinfunction "RXD_3") (pintype "passive"))
    )
    (net (code "79") (name "Net-(U5-TXD)") (class "Default")
      (node (ref "R36") (pin "2") (pinfunction "2_2") (pintype "passive"))
      (node (ref "U5") (pin "2") (pinfunction "TXD_2") (pintype "passive"))
    )
    (net (code "80") (name "Net-(U5-V3)") (class "Default")
      (node (ref "C23") (pin "1") (pinfunction "1_1") (pintype "passive"))
      (node (ref "U5") (pin "4") (pinfunction "V3_4") (pintype "passive"))
    )
    (net (code "81") (name "VCC_5V") (class "Default")
      (node (ref "C16") (pin "1") (pinfunction "1_1") (pintype "passive"))
      (node (ref "C19") (pin "1") (pinfunction "1_1") (pintype "passive"))
      (node (ref "C20") (pin "2") (pinfunction "2_2") (pintype "passive"))
      (node (ref "U5") (pin "16") (pinfunction "VCC_16") (pintype "passive"))
      (node (ref "U6") (pin "3") (pinfunction "IN_3") (pintype "passive"))
      (node (ref "U7") (pin "4") (pinfunction "OUT_4") (pintype "passive"))
      (node (ref "USB1") (pin "1") (pinfunction "+5V_1") (pintype "passive"))
    )
    (net (code "82") (name "VCC_BLUE") (class "Default")
      (node (ref "C1") (pin "1") (pinfunction "1_1") (pintype "passive"))
      (node (ref "Q2") (pin "3") (pinfunction "D_3") (pintype "passive"))
      (node (ref "U1") (pin "2") (pinfunction "VCC_2") (pintype "passive"))
    )
    (net (code "83") (name "VCC_NB") (class "Default")
      (node (ref "C2") (pin "1") (pinfunction "1_1") (pintype "passive"))
      (node (ref "C3") (pin "2") (pinfunction "2_2") (pintype "passive"))
      (node (ref "Q4") (pin "3") (pinfunction "D_3") (pintype "passive"))
      (node (ref "U2") (pin "39") (pinfunction "VBAT_39") (pintype "passive"))
      (node (ref "U2") (pin "40") (pinfunction "VBAT_40") (pintype "passive"))
    )
    (net (code "84") (name "unconnected-(U1-P17-Pad11)") (class "Default")
      (node (ref "U1") (pin "11") (pinfunction "P17_11") (pintype "passive"))
    )
    (net (code "85") (name "unconnected-(U1-P27-Pad3)") (class "Default")
      (node (ref "U1") (pin "3") (pinfunction "P27_3") (pintype "passive"))
    )
    (net (code "86") (name "unconnected-(U1-P28{slash}AIN4-Pad4)") (class "Default")
      (node (ref "U1") (pin "4") (pinfunction "P28/AIN4_4") (pintype "passive"))
    )
    (net (code "87") (name "unconnected-(U1-P29{slash}AIN5-Pad5)") (class "Default")
      (node (ref "U1") (pin "5") (pinfunction "P29/AIN5_5") (pintype "passive"))
    )
    (net (code "88") (name "unconnected-(U1-P30{slash}AIN6-Pad6)") (class "Default")
      (node (ref "U1") (pin "6") (pinfunction "P30/AIN6_6") (pintype "passive"))
    )
    (net (code "89") (name "unconnected-(U1-P31{slash}AIN7-Pad7)") (class "Default")
      (node (ref "U1") (pin "7") (pinfunction "P31/AIN7_7") (pintype "passive"))
    )
    (net (code "90") (name "unconnected-(U1-SWCLK-Pad15)") (class "Default")
      (node (ref "U1") (pin "15") (pinfunction "SWCLK_15") (pintype "passive"))
    )
    (net (code "91") (name "unconnected-(U1-SWDIO-Pad16)") (class "Default")
      (node (ref "U1") (pin "16") (pinfunction "SWDIO_16") (pintype "passive"))
    )
    (net (code "92") (name "unconnected-(U2-ADC-Pad33)") (class "Default")
      (node (ref "U2") (pin "33") (pinfunction "ADC_33") (pintype "passive"))
    )
    (net (code "93") (name "unconnected-(U2-AIO<0>-Pad32)") (class "Default")
      (node (ref "U2") (pin "32") (pinfunction "AIO<0>_32") (pintype "passive"))
    )
    (net (code "94") (name "unconnected-(U2-DBG_RXD-Pad25)") (class "Default")
      (node (ref "U2") (pin "25") (pinfunction "DBG_RXD_25") (pintype "passive"))
    )
    (net (code "95") (name "unconnected-(U2-DBG_TXD-Pad26)") (class "Default")
      (node (ref "U2") (pin "26") (pinfunction "DBG_TXD_26") (pintype "passive"))
    )
    (net (code "96") (name "unconnected-(U2-GPIO11-Pad6)") (class "Default")
      (node (ref "U2") (pin "6") (pinfunction "GPIO11_6") (pintype "passive"))
    )
    (net (code "97") (name "unconnected-(U2-NC-Pad3)") (class "Default")
      (node (ref "U2") (pin "3") (pinfunction "NC_3") (pintype "passive"))
    )
    (net (code "98") (name "unconnected-(U2-NC-Pad4)") (class "Default")
      (node (ref "U2") (pin "4") (pinfunction "NC_4") (pintype "passive"))
    )
    (net (code "99") (name "unconnected-(U2-NC-Pad5)") (class "Default")
      (node (ref "U2") (pin "5") (pinfunction "NC_5") (pintype "passive"))
    )
    (net (code "100") (name "unconnected-(U2-NC-Pad8)") (class "Default")
      (node (ref "U2") (pin "8") (pinfunction "NC_8") (pintype "passive"))
    )
    (net (code "101") (name "unconnected-(U2-NC-Pad10)") (class "Default")
      (node (ref "U2") (pin "10") (pinfunction "NC_10") (pintype "passive"))
    )
    (net (code "102") (name "unconnected-(U2-NC-Pad11)") (class "Default")
      (node (ref "U2") (pin "11") (pinfunction "NC_11") (pintype "passive"))
    )
    (net (code "103") (name "unconnected-(U2-NC-Pad12)") (class "Default")
      (node (ref "U2") (pin "12") (pinfunction "NC_12") (pintype "passive"))
    )
    (net (code "104") (name "unconnected-(U2-RI-Pad34)") (class "Default")
      (node (ref "U2") (pin "34") (pinfunction "RI_34") (pintype "passive"))
    )
    (net (code "105") (name "unconnected-(U2-RIO<1>-Pad9)") (class "Default")
      (node (ref "U2") (pin "9") (pinfunction "RIO<1>_9") (pintype "passive"))
    )
    (net (code "106") (name "unconnected-(U2-SWD_DIO-Pad36)") (class "Default")
      (node (ref "U2") (pin "36") (pinfunction "SWD_DIO_36") (pintype "passive"))
    )
    (net (code "107") (name "unconnected-(U2-VDD_EXT-Pad7)") (class "Default")
      (node (ref "U2") (pin "7") (pinfunction "VDD_EXT_7") (pintype "passive"))
    )
    (net (code "108") (name "unconnected-(U3-VPP-Pad5)") (class "Default")
      (node (ref "U3") (pin "5") (pinfunction "VPP_5") (pintype "passive"))
    )
    (net (code "109") (name "unconnected-(U4-PA11-Pad32)") (class "Default")
      (node (ref "U4") (pin "32") (pinfunction "PA11_32") (pintype "bidirectional"))
    )
    (net (code "110") (name "unconnected-(U4-PA15{slash}JTDI-Pad38)") (class "Default")
      (node (ref "U4") (pin "38") (pinfunction "PA15/JTDI_38") (pintype "bidirectional"))
    )
    (net (code "111") (name "unconnected-(U4-PB0-Pad18)") (class "Default")
      (node (ref "U4") (pin "18") (pinfunction "PB0_18") (pintype "bidirectional"))
    )
    (net (code "112") (name "unconnected-(U4-PB1-Pad19)") (class "Default")
      (node (ref "U4") (pin "19") (pinfunction "PB1_19") (pintype "bidirectional"))
    )
    (net (code "113") (name "unconnected-(U4-PB15-Pad28)") (class "Default")
      (node (ref "U4") (pin "28") (pinfunction "PB15_28") (pintype "bidirectional"))
    )
    (net (code "114") (name "unconnected-(U4-PC13-TAMPER-RTC-Pad2)") (class "Default")
      (node (ref "U4") (pin "2") (pinfunction "PC13-TAMPER-RTC_2") (pintype "bidirectional"))
    )
    (net (code "115") (name "unconnected-(U5-CTS-Pad9)") (class "Default")
      (node (ref "U5") (pin "9") (pinfunction "CTS_9") (pintype "passive"))
    )
    (net (code "116") (name "unconnected-(U5-DSR-Pad10)") (class "Default")
      (node (ref "U5") (pin "10") (pinfunction "DSR_10") (pintype "passive"))
    )
    (net (code "117") (name "unconnected-(U5-DTR-Pad13)") (class "Default")
      (node (ref "U5") (pin "13") (pinfunction "DTR_13") (pintype "passive"))
    )
    (net (code "118") (name "unconnected-(U5-R233-Pad15)") (class "Default")
      (node (ref "U5") (pin "15") (pinfunction "R233_15") (pintype "passive"))
    )
    (net (code "119") (name "unconnected-(U5-RCD-Pad12)") (class "Default")
      (node (ref "U5") (pin "12") (pinfunction "RCD_12") (pintype "passive"))
    )
    (net (code "120") (name "unconnected-(U5-RI-Pad11)") (class "Default")
      (node (ref "U5") (pin "11") (pinfunction "RI_11") (pintype "passive"))
    )
    (net (code "121") (name "unconnected-(U5-RTS-Pad14)") (class "Default")
      (node (ref "U5") (pin "14") (pinfunction "RTS_14") (pintype "passive"))
    )
    (net (code "122") (name "unconnected-(U5-XD-Pad8)") (class "Default")
      (node (ref "U5") (pin "8") (pinfunction "XD_8") (pintype "passive"))
    )
    (net (code "123") (name "unconnected-(U5-XI-Pad7)") (class "Default")
      (node (ref "U5") (pin "7") (pinfunction "XI_7") (pintype "passive"))
    )
    (net (code "124") (name "unconnected-(U7-OUT-Pad2)") (class "Default")
      (node (ref "U7") (pin "2") (pinfunction "OUT_2") (pintype "passive"))
    )
    (net (code "125") (name "unconnected-(X1-Pad2)") (class "Default")
      (node (ref "X1") (pin "2") (pinfunction "2_2") (pintype "passive"))
    )
    (net (code "126") (name "unconnected-(X1-Pad4)") (class "Default")
      (node (ref "X1") (pin "4") (pinfunction "4_4") (pintype "passive"))
    )
  )
)
